# qo-100-pa-driver.net
KiCad netlist of a schematic drawn in EAGLE
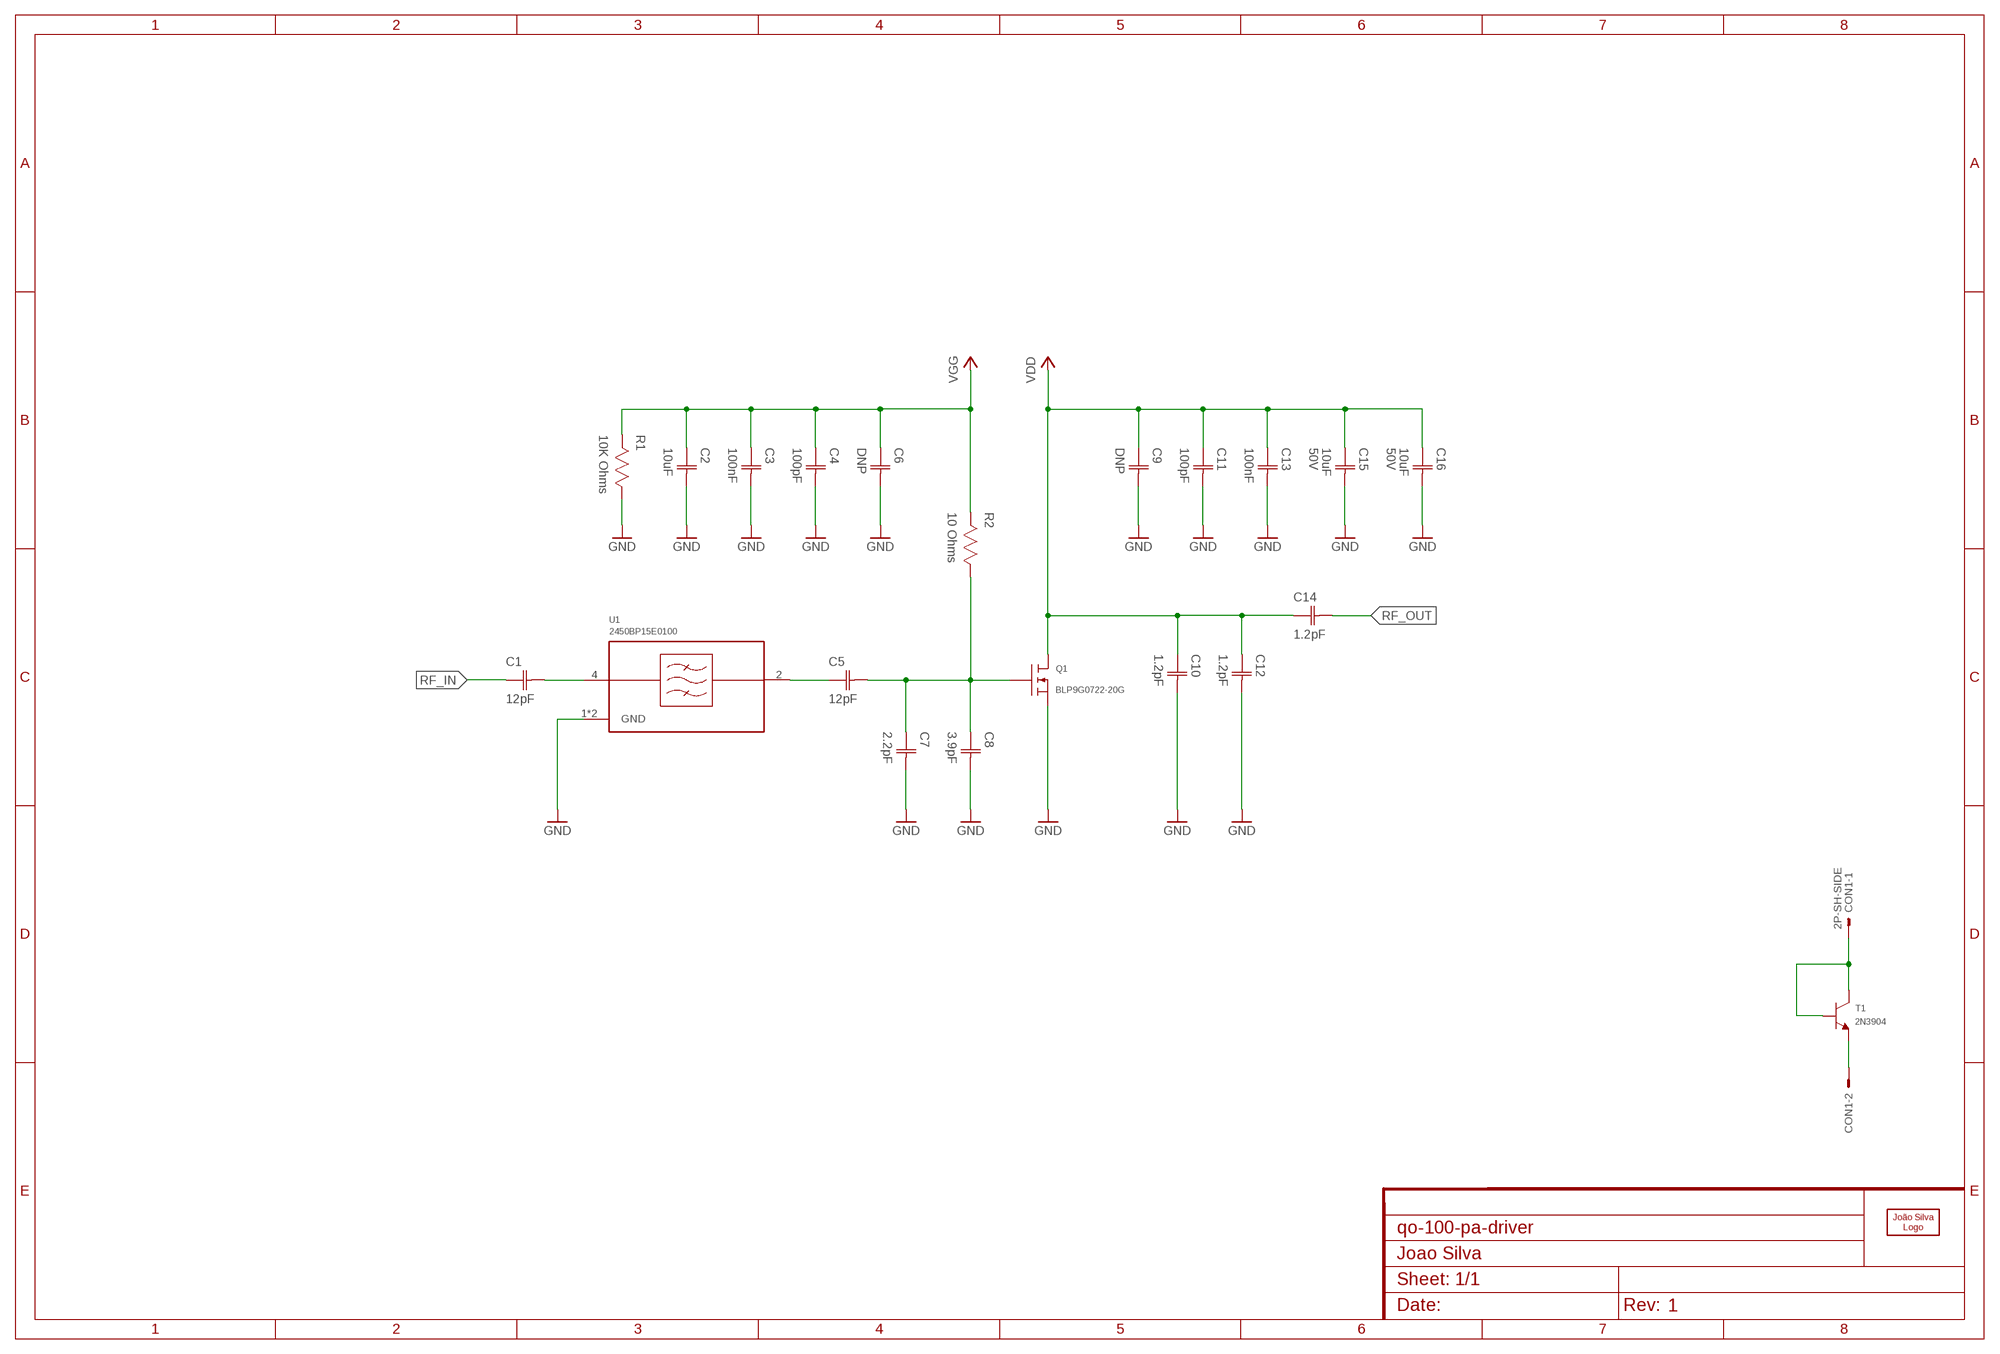
[diagram p0: schematic, sheet 1]

(export (version "E")
  (design (tool "Eeschema 10.0.6"))
  (components
    (comp (ref "C1")
      (value "12pF")
      (footprint "eagle-import:CAP0603")
      (libsource (lib "eagle-import") (part "CAPACITOR-0603"))
    )
    (comp (ref "C2")
      (value "10uF")
      (footprint "eagle-import:CAP0603")
      (libsource (lib "eagle-import") (part "CAPACITOR-0603"))
    )
    (comp (ref "C3")
      (value "100nF")
      (footprint "eagle-import:CAP0603")
      (libsource (lib "eagle-import") (part "CAPACITOR-0603"))
    )
    (comp (ref "C4")
      (value "100pF")
      (footprint "eagle-import:CAP0603")
      (libsource (lib "eagle-import") (part "CAPACITOR-0603"))
    )
    (comp (ref "C5")
      (value "12pF")
      (footprint "eagle-import:CAP0603")
      (libsource (lib "eagle-import") (part "CAPACITOR-0603"))
    )
    (comp (ref "C6")
      (value "DNP")
      (footprint "eagle-import:CAP0603")
      (libsource (lib "eagle-import") (part "CAPACITOR-0603"))
    )
    (comp (ref "C7")
      (value "2.2pF")
      (footprint "eagle-import:CAP0603")
      (libsource (lib "eagle-import") (part "CAPACITOR-0603"))
    )
    (comp (ref "C8")
      (value "3.9pF")
      (footprint "eagle-import:CAP0603")
      (libsource (lib "eagle-import") (part "CAPACITOR-0603"))
    )
    (comp (ref "C9")
      (value "DNP")
      (footprint "eagle-import:CAP0603")
      (libsource (lib "eagle-import") (part "CAPACITOR-0603"))
    )
    (comp (ref "C10")
      (value "1.2pF")
      (footprint "eagle-import:CAP0603")
      (libsource (lib "eagle-import") (part "CAPACITOR-0603"))
    )
    (comp (ref "C11")
      (value "100pF")
      (footprint "eagle-import:CAP0603")
      (libsource (lib "eagle-import") (part "CAPACITOR-0603"))
    )
    (comp (ref "C12")
      (value "1.2pF")
      (footprint "eagle-import:CAP0603")
      (libsource (lib "eagle-import") (part "CAPACITOR-0603"))
    )
    (comp (ref "C13")
      (value "100nF")
      (footprint "eagle-import:CAP0603")
      (libsource (lib "eagle-import") (part "CAPACITOR-0603"))
    )
    (comp (ref "C14")
      (value "1.2pF")
      (footprint "eagle-import:CAP0603")
      (libsource (lib "eagle-import") (part "CAPACITOR-0603"))
    )
    (comp (ref "C15")
      (value "10uF")
      (footprint "eagle-import:CAP1206")
      (fields (field (name "VOLTAGE") "50V"))
      (libsource (lib "eagle-import") (part "CAPACITOR-1206"))
    )
    (comp (ref "C16")
      (value "10uF")
      (footprint "eagle-import:CAP1206")
      (fields (field (name "VOLTAGE") "50V"))
      (libsource (lib "eagle-import") (part "CAPACITOR-1206"))
    )
    (comp (ref "CON1")
      (value "2P-SH-SIDE")
      (footprint "eagle-import:SH-02-SIDE")
      (libsource (lib "eagle-import") (part "2P-SH-SIDE"))
    )
    (comp (ref "LOGO1")
      (value "JS-5MM")
      (footprint "eagle-import:JS_5MM")
      (libsource (lib "eagle-import") (part "JS-5MM"))
    )
    (comp (ref "Q1")
      (value "BLP9G0722-20G")
      (footprint "eagle-import:SOT1483-1")
      (libsource (lib "eagle-import") (part "BLP9G0722-20G"))
    )
    (comp (ref "R1")
      (value "10K Ohms")
      (footprint "eagle-import:RES0603")
      (libsource (lib "eagle-import") (part "RESISTOR-0603"))
    )
    (comp (ref "R2")
      (value "10 Ohms")
      (footprint "eagle-import:RES0603")
      (libsource (lib "eagle-import") (part "RESISTOR-0603"))
    )
    (comp (ref "T1")
      (value "2N3904")
      (footprint "eagle-import:SOT23")
      (libsource (lib "eagle-import") (part "2N3904"))
    )
    (comp (ref "U1")
      (value "2450BP15E0100")
      (footprint "eagle-import:2450BP15E0100")
      (libsource (lib "eagle-import") (part "2450BP15E0100"))
    )
  )
  (nets
    (net (code "1") (name "GND") (class "Default")
      (node (ref "C10") (pin "2") (pinfunction "C2_2") (pintype "passive"))
      (node (ref "C11") (pin "2") (pinfunction "C2_2") (pintype "passive"))
      (node (ref "C12") (pin "2") (pinfunction "C2_2") (pintype "passive"))
      (node (ref "C13") (pin "2") (pinfunction "C2_2") (pintype "passive"))
      (node (ref "C15") (pin "2") (pinfunction "C2_2") (pintype "passive"))
      (node (ref "C16") (pin "2") (pinfunction "C2_2") (pintype "passive"))
      (node (ref "C2") (pin "2") (pinfunction "C2_2") (pintype "passive"))
      (node (ref "C3") (pin "2") (pinfunction "C2_2") (pintype "passive"))
      (node (ref "C4") (pin "2") (pinfunction "C2_2") (pintype "passive"))
      (node (ref "C6") (pin "2") (pinfunction "C2_2") (pintype "passive"))
      (node (ref "C7") (pin "2") (pinfunction "C2_2") (pintype "passive"))
      (node (ref "C8") (pin "2") (pinfunction "C2_2") (pintype "passive"))
      (node (ref "C9") (pin "2") (pinfunction "C2_2") (pintype "passive"))
      (node (ref "Q1") (pin "3@0") (pinfunction "S_3@0") (pintype "passive"))
      (node (ref "Q1") (pin "3@1") (pinfunction "S_3@1") (pintype "passive"))
      (node (ref "Q1") (pin "3@2") (pinfunction "S_3@2") (pintype "passive"))
      (node (ref "R1") (pin "1") (pinfunction "1_1") (pintype "passive"))
      (node (ref "U1") (pin "1") (pinfunction "GND_1") (pintype "bidirectional"))
      (node (ref "U1") (pin "3") (pinfunction "GND_3") (pintype "bidirectional"))
    )
    (net (code "2") (name "Net-(C1-C2)") (class "Default")
      (node (ref "C1") (pin "2") (pinfunction "C2_2") (pintype "passive"))
      (node (ref "U1") (pin "4") (pinfunction "RFIN_4") (pintype "bidirectional"))
    )
    (net (code "3") (name "Net-(C5-C1)") (class "Default")
      (node (ref "C5") (pin "1") (pinfunction "C1_1") (pintype "passive"))
      (node (ref "U1") (pin "2") (pinfunction "RFOUT_2") (pintype "bidirectional"))
    )
    (net (code "4") (name "Net-(C5-C2)") (class "Default")
      (node (ref "C5") (pin "2") (pinfunction "C2_2") (pintype "passive"))
      (node (ref "C7") (pin "1") (pinfunction "C1_1") (pintype "passive"))
      (node (ref "C8") (pin "1") (pinfunction "C1_1") (pintype "passive"))
      (node (ref "Q1") (pin "2") (pinfunction "G_2") (pintype "passive"))
      (node (ref "R2") (pin "1") (pinfunction "1_1") (pintype "passive"))
    )
    (net (code "5") (name "Net-(CON1A-S)") (class "Default")
      (node (ref "CON1") (pin "1") (pinfunction "S_1") (pintype "passive"))
      (node (ref "T1") (pin "1") (pinfunction "B_1") (pintype "passive"))
      (node (ref "T1") (pin "3") (pinfunction "C_3") (pintype "passive"))
    )
    (net (code "6") (name "Net-(CON1B-S)") (class "Default")
      (node (ref "CON1") (pin "2") (pinfunction "S_2") (pintype "passive"))
      (node (ref "T1") (pin "2") (pinfunction "E_2") (pintype "passive"))
    )
    (net (code "7") (name "RF_IN") (class "Default")
      (node (ref "C1") (pin "1") (pinfunction "C1_1") (pintype "passive"))
    )
    (net (code "8") (name "RF_OUT") (class "Default")
      (node (ref "C14") (pin "2") (pinfunction "C2_2") (pintype "passive"))
    )
    (net (code "9") (name "VDD") (class "Default")
      (node (ref "C10") (pin "1") (pinfunction "C1_1") (pintype "passive"))
      (node (ref "C11") (pin "1") (pinfunction "C1_1") (pintype "passive"))
      (node (ref "C12") (pin "1") (pinfunction "C1_1") (pintype "passive"))
      (node (ref "C13") (pin "1") (pinfunction "C1_1") (pintype "passive"))
      (node (ref "C14") (pin "1") (pinfunction "C1_1") (pintype "passive"))
      (node (ref "C15") (pin "1") (pinfunction "C1_1") (pintype "passive"))
      (node (ref "C16") (pin "1") (pinfunction "C1_1") (pintype "passive"))
      (node (ref "C9") (pin "1") (pinfunction "C1_1") (pintype "passive"))
      (node (ref "Q1") (pin "1") (pinfunction "D_1") (pintype "passive"))
    )
    (net (code "10") (name "VGG") (class "Default")
      (node (ref "C2") (pin "1") (pinfunction "C1_1") (pintype "passive"))
      (node (ref "C3") (pin "1") (pinfunction "C1_1") (pintype "passive"))
      (node (ref "C4") (pin "1") (pinfunction "C1_1") (pintype "passive"))
      (node (ref "C6") (pin "1") (pinfunction "C1_1") (pintype "passive"))
      (node (ref "R1") (pin "2") (pinfunction "2_2") (pintype "passive"))
      (node (ref "R2") (pin "2") (pinfunction "2_2") (pintype "passive"))
    )
  )
)
